# Modu_zasilania_12V.net
KiCad netlist of a schematic drawn in EAGLE
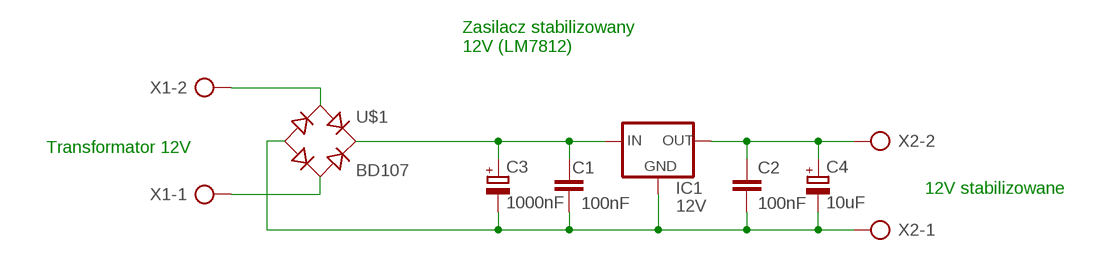
[diagram p0: schematic, sheet 1]

(export (version "E")
  (design (tool "Eeschema 10.0.6"))
  (components
    (comp (ref "C1")
      (value "100nF")
      (footprint "eagle-import:C50-45-75")
      (libsource (lib "eagle-import") (part "C-EU050-045-075"))
    )
    (comp (ref "C2")
      (value "100nF")
      (footprint "eagle-import:C50-45-75")
      (libsource (lib "eagle-import") (part "C-EU050-045-075"))
    )
    (comp (ref "C3")
      (value "1000nF")
      (footprint "eagle-import:E5-13")
      (libsource (lib "eagle-import") (part "C-EU-POL"))
    )
    (comp (ref "C4")
      (value "10uF")
      (footprint "eagle-import:E2,5-6")
      (libsource (lib "eagle-import") (part "C-EU-POL'"))
    )
    (comp (ref "IC1")
      (value "12V")
      (footprint "eagle-import:78XXS")
      (libsource (lib "eagle-import") (part "78XXS"))
    )
    (comp (ref "U$1")
      (value "BD107")
      (footprint "eagle-import:B-DIL")
      (libsource (lib "eagle-import") (part "BD107"))
    )
    (comp (ref "X1")
      (value "AK300/2")
      (footprint "eagle-import:AK300_2")
      (libsource (lib "eagle-import") (part "AK300/2"))
    )
    (comp (ref "X2")
      (value "AK300/2")
      (footprint "eagle-import:AK300_2")
      (libsource (lib "eagle-import") (part "AK300/2"))
    )
  )
  (nets
    (net (code "1") (name "Net-(C1-1)") (class "Default")
      (node (ref "C1") (pin "P$1") (pinfunction "1_P$1") (pintype "passive"))
      (node (ref "C2") (pin "P$2") (pinfunction "2_P$2") (pintype "passive"))
      (node (ref "C3") (pin "P$2") (pinfunction "-_P$2") (pintype "passive"))
      (node (ref "C4") (pin "P$2") (pinfunction "-_P$2") (pintype "passive"))
      (node (ref "IC1") (pin "GND") (pinfunction "GND_GND") (pintype "input"))
      (node (ref "U$1") (pin "-") (pinfunction "-_-") (pintype "passive"))
      (node (ref "X2") (pin "1") (pinfunction "KL_1") (pintype "passive"))
    )
    (net (code "2") (name "Net-(C1-2)") (class "Default")
      (node (ref "C1") (pin "P$2") (pinfunction "2_P$2") (pintype "passive"))
      (node (ref "C3") (pin "P$1") (pinfunction "+_P$1") (pintype "passive"))
      (node (ref "IC1") (pin "IN") (pinfunction "IN_IN") (pintype "input"))
      (node (ref "U$1") (pin "+") (pinfunction "+_+") (pintype "passive"))
    )
    (net (code "3") (name "Net-(C2-1)") (class "Default")
      (node (ref "C2") (pin "P$1") (pinfunction "1_P$1") (pintype "passive"))
      (node (ref "C4") (pin "P$1") (pinfunction "+_P$1") (pintype "passive"))
      (node (ref "IC1") (pin "OUT") (pinfunction "OUT_OUT") (pintype "passive"))
      (node (ref "X2") (pin "2") (pinfunction "KL_2") (pintype "passive"))
    )
    (net (code "4") (name "Net-(X1A-KL)") (class "Default")
      (node (ref "U$1") (pin "AC2") (pinfunction "AC2_AC2") (pintype "passive"))
      (node (ref "X1") (pin "1") (pinfunction "KL_1") (pintype "passive"))
    )
    (net (code "5") (name "Net-(X1B-KL)") (class "Default")
      (node (ref "U$1") (pin "AC1") (pinfunction "AC1_AC1") (pintype "passive"))
      (node (ref "X1") (pin "2") (pinfunction "KL_2") (pintype "passive"))
    )
  )
)
